# 3_Phase_Controller_V0_2.net
KiCad netlist of a schematic drawn in EAGLE
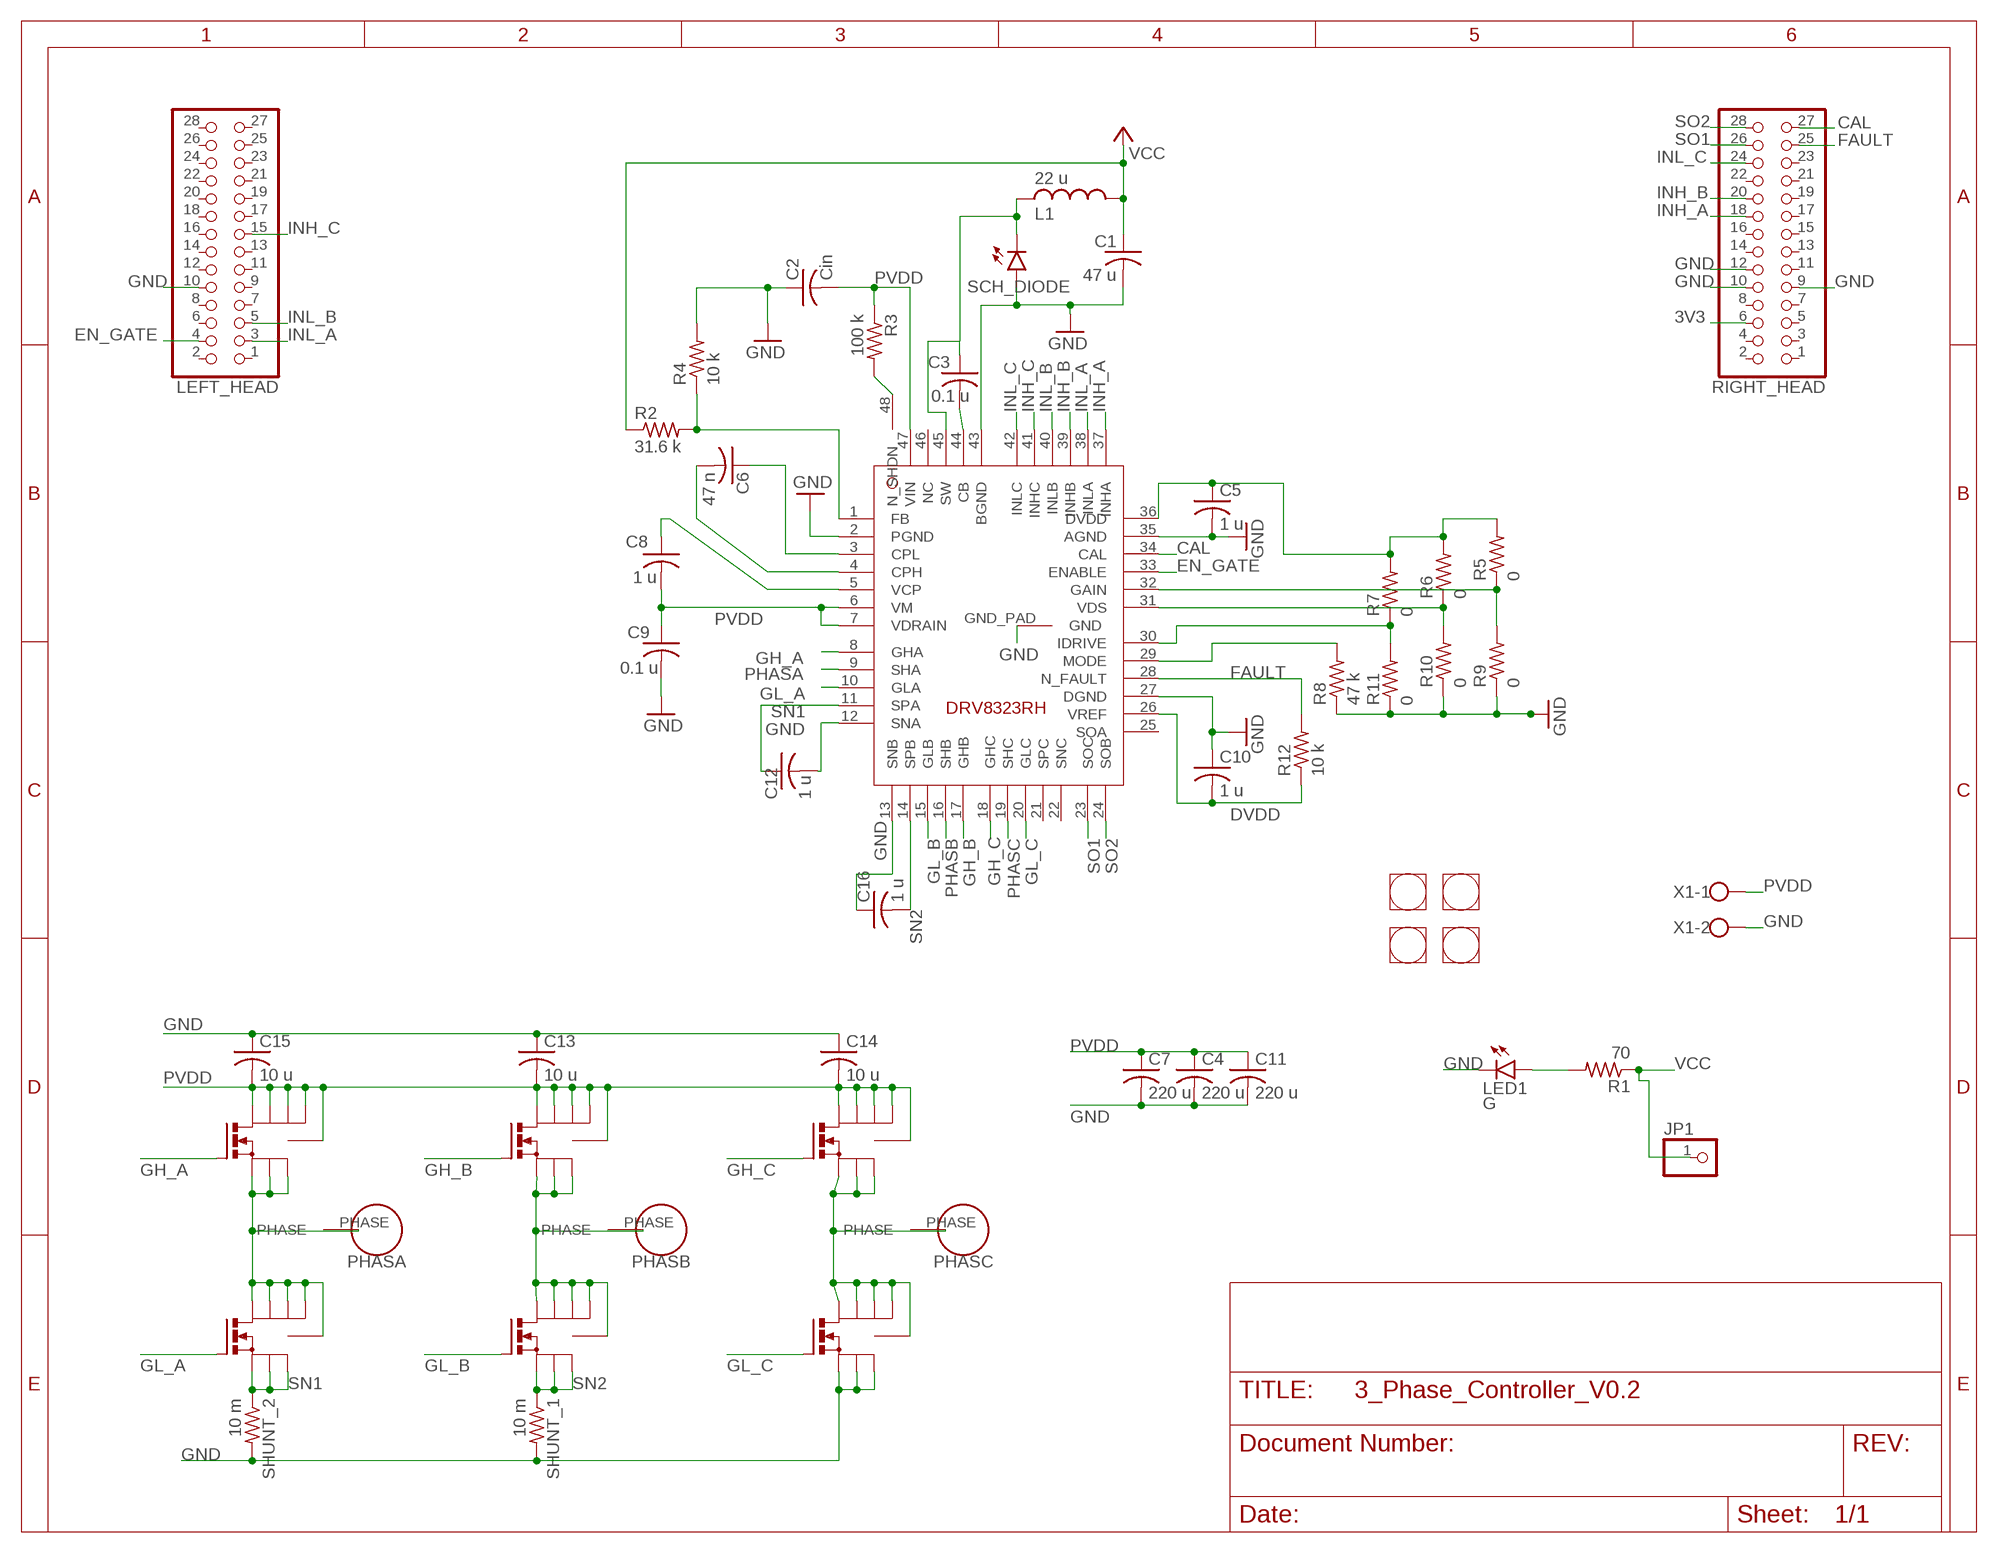
[diagram p0: schematic, sheet 1]

(export (version "E")
  (design (tool "Eeschema 10.0.6"))
  (components
    (comp (ref "A_H")
      (value "SIR178DP")
      (footprint "eagle-import:POWERPAK_SO-8_SINGLE")
      (libsource (lib "eagle-import") (part "SIR178DP"))
    )
    (comp (ref "A_L")
      (value "SIR178DP")
      (footprint "eagle-import:POWERPAK_SO-8_SINGLE")
      (libsource (lib "eagle-import") (part "SIR178DP"))
    )
    (comp (ref "B_H")
      (value "SIR178DP")
      (footprint "eagle-import:POWERPAK_SO-8_SINGLE")
      (libsource (lib "eagle-import") (part "SIR178DP"))
    )
    (comp (ref "B_L")
      (value "SIR178DP")
      (footprint "eagle-import:POWERPAK_SO-8_SINGLE")
      (libsource (lib "eagle-import") (part "SIR178DP"))
    )
    (comp (ref "C1")
      (value "47 u")
      (footprint "eagle-import:C025-024X044")
      (libsource (lib "eagle-import") (part "C-US025-024X044"))
    )
    (comp (ref "C2")
      (value "Cin")
      (footprint "eagle-import:C0805")
      (libsource (lib "eagle-import") (part "C-USC0805"))
    )
    (comp (ref "C3")
      (value "0.1 u")
      (footprint "eagle-import:C0805")
      (libsource (lib "eagle-import") (part "C-USC0805"))
    )
    (comp (ref "C4")
      (value "220 u")
      (footprint "eagle-import:C050-045X075")
      (libsource (lib "eagle-import") (part "C-US050-045X075"))
    )
    (comp (ref "C5")
      (value "1 u")
      (footprint "eagle-import:C0805")
      (libsource (lib "eagle-import") (part "C-USC0805"))
    )
    (comp (ref "C6")
      (value "47 n")
      (footprint "eagle-import:C0805")
      (libsource (lib "eagle-import") (part "C-USC0805"))
    )
    (comp (ref "C7")
      (value "220 u")
      (footprint "eagle-import:C050-045X075")
      (libsource (lib "eagle-import") (part "C-US050-045X075"))
    )
    (comp (ref "C8")
      (value "1 u")
      (footprint "eagle-import:C0805")
      (libsource (lib "eagle-import") (part "C-USC0805"))
    )
    (comp (ref "C9")
      (value "0.1 u")
      (footprint "eagle-import:C0805")
      (libsource (lib "eagle-import") (part "C-USC0805"))
    )
    (comp (ref "C10")
      (value "1 u")
      (footprint "eagle-import:C0805")
      (libsource (lib "eagle-import") (part "C-USC0805"))
    )
    (comp (ref "C11")
      (value "220 u")
      (footprint "eagle-import:C050-045X075")
      (libsource (lib "eagle-import") (part "C-US050-045X075"))
    )
    (comp (ref "C12")
      (value "1 u")
      (footprint "eagle-import:C0805")
      (libsource (lib "eagle-import") (part "C-USC0805"))
    )
    (comp (ref "C13")
      (value "10 u")
      (footprint "eagle-import:C1206")
      (libsource (lib "eagle-import") (part "C-USC1206"))
    )
    (comp (ref "C14")
      (value "10 u")
      (footprint "eagle-import:C1206")
      (libsource (lib "eagle-import") (part "C-USC1206"))
    )
    (comp (ref "C15")
      (value "10 u")
      (footprint "eagle-import:C1206")
      (libsource (lib "eagle-import") (part "C-USC1206"))
    )
    (comp (ref "C16")
      (value "1 u")
      (footprint "eagle-import:C0805")
      (libsource (lib "eagle-import") (part "C-USC0805"))
    )
    (comp (ref "C_H")
      (value "SIR178DP")
      (footprint "eagle-import:POWERPAK_SO-8_SINGLE")
      (libsource (lib "eagle-import") (part "SIR178DP"))
    )
    (comp (ref "C_L")
      (value "SIR178DP")
      (footprint "eagle-import:POWERPAK_SO-8_SINGLE")
      (libsource (lib "eagle-import") (part "SIR178DP"))
    )
    (comp (ref "JP1")
      (value "PINHD-1X1")
      (footprint "eagle-import:1X01")
      (libsource (lib "eagle-import") (part "PINHD-1X1"))
    )
    (comp (ref "L1")
      (value "22 u")
      (footprint "eagle-import:L3225M")
      (libsource (lib "eagle-import") (part "L-USL3225M"))
    )
    (comp (ref "LED1")
      (value "G")
      (footprint "eagle-import:SML0805")
      (libsource (lib "eagle-import") (part "LEDSML0805"))
    )
    (comp (ref "LEFT_HEAD")
      (value "PINHD-2X14")
      (footprint "eagle-import:2X14")
      (libsource (lib "eagle-import") (part "PINHD-2X14"))
    )
    (comp (ref "PHASE_A")
      (value "PHASE_HOLE_V_0.2")
      (footprint "eagle-import:HOLE_V_0.2")
      (libsource (lib "eagle-import") (part "PHASE_HOLE_V_0.2"))
    )
    (comp (ref "PHASE_B")
      (value "PHASE_HOLE_V_0.2")
      (footprint "eagle-import:HOLE_V_0.2")
      (libsource (lib "eagle-import") (part "PHASE_HOLE_V_0.2"))
    )
    (comp (ref "PHASE_C")
      (value "PHASE_HOLE_V_0.2")
      (footprint "eagle-import:HOLE_V_0.2")
      (libsource (lib "eagle-import") (part "PHASE_HOLE_V_0.2"))
    )
    (comp (ref "R1")
      (value "70")
      (footprint "eagle-import:R0805")
      (libsource (lib "eagle-import") (part "R-US_R0805"))
    )
    (comp (ref "R2")
      (value "31.6 k")
      (footprint "eagle-import:R0603")
      (libsource (lib "eagle-import") (part "R-US_R0603"))
    )
    (comp (ref "R3")
      (value "100 k")
      (footprint "eagle-import:R0805")
      (libsource (lib "eagle-import") (part "R-US_R0805"))
    )
    (comp (ref "R4")
      (value "10 k")
      (footprint "eagle-import:R0603")
      (libsource (lib "eagle-import") (part "R-US_R0603"))
    )
    (comp (ref "R5")
      (value "0")
      (footprint "eagle-import:R0603")
      (libsource (lib "eagle-import") (part "R-US_R0603"))
    )
    (comp (ref "R6")
      (value "0")
      (footprint "eagle-import:R0603")
      (libsource (lib "eagle-import") (part "R-US_R0603"))
    )
    (comp (ref "R7")
      (value "0")
      (footprint "eagle-import:R0603")
      (libsource (lib "eagle-import") (part "R-US_R0603"))
    )
    (comp (ref "R8")
      (value "47 k")
      (footprint "eagle-import:R0603")
      (libsource (lib "eagle-import") (part "R-US_R0603"))
    )
    (comp (ref "R9")
      (value "0")
      (footprint "eagle-import:R0603")
      (libsource (lib "eagle-import") (part "R-US_R0603"))
    )
    (comp (ref "R10")
      (value "0")
      (footprint "eagle-import:R0603")
      (libsource (lib "eagle-import") (part "R-US_R0603"))
    )
    (comp (ref "R11")
      (value "0")
      (footprint "eagle-import:R0603")
      (libsource (lib "eagle-import") (part "R-US_R0603"))
    )
    (comp (ref "R12")
      (value "10 k")
      (footprint "eagle-import:R0603")
      (libsource (lib "eagle-import") (part "R-US_R0603"))
    )
    (comp (ref "RIGHT_HEAD")
      (value "PINHD-2X14")
      (footprint "eagle-import:2X14")
      (libsource (lib "eagle-import") (part "PINHD-2X14"))
    )
    (comp (ref "SCH_DIODE")
      (value "LEDCHIP-LED0805")
      (footprint "eagle-import:CHIP-LED0805")
      (libsource (lib "eagle-import") (part "LEDCHIP-LED0805"))
    )
    (comp (ref "SHUNT_1")
      (value "10 m")
      (footprint "eagle-import:R2512")
      (libsource (lib "eagle-import") (part "R-US_R2512"))
    )
    (comp (ref "SHUNT_2")
      (value "10 m")
      (footprint "eagle-import:R2512")
      (libsource (lib "eagle-import") (part "R-US_R2512"))
    )
    (comp (ref "U$1")
      (value "STANDOFF")
      (footprint "eagle-import:STANDOFF")
      (libsource (lib "eagle-import") (part "STANDOFF"))
    )
    (comp (ref "U$2")
      (value "STANDOFF")
      (footprint "eagle-import:STANDOFF")
      (libsource (lib "eagle-import") (part "STANDOFF"))
    )
    (comp (ref "U$3")
      (value "DRV8323RH")
      (footprint "eagle-import:VQFN-RGZ0048A")
      (libsource (lib "eagle-import") (part "DRV8323RH"))
    )
    (comp (ref "U$4")
      (value "STANDOFF")
      (footprint "eagle-import:STANDOFF")
      (libsource (lib "eagle-import") (part "STANDOFF"))
    )
    (comp (ref "U$5")
      (value "STANDOFF")
      (footprint "eagle-import:STANDOFF")
      (libsource (lib "eagle-import") (part "STANDOFF"))
    )
    (comp (ref "X1")
      (value "W237-102")
      (footprint "eagle-import:W237-102")
      (fields (field (name "MPN") "237-102"))
      (libsource (lib "eagle-import") (part "W237-102"))
    )
  )
  (nets
    (net (code "1") (name "/3V3") (class "Default")
      (node (ref "RIGHT_HEAD") (pin "6") (pinfunction "6_6") (pintype "passive"))
    )
    (net (code "2") (name "/CAL") (class "Default")
      (node (ref "RIGHT_HEAD") (pin "27") (pinfunction "27_27") (pintype "passive"))
      (node (ref "U$3") (pin "34") (pinfunction "CAL_34") (pintype "bidirectional"))
    )
    (net (code "3") (name "/DVDD") (class "Default")
      (node (ref "C10") (pin "2") (pinfunction "2_2") (pintype "passive"))
      (node (ref "C5") (pin "1") (pinfunction "1_1") (pintype "passive"))
      (node (ref "R12") (pin "1") (pinfunction "1_1") (pintype "passive"))
      (node (ref "R5") (pin "2") (pinfunction "2_2") (pintype "passive"))
      (node (ref "R6") (pin "2") (pinfunction "2_2") (pintype "passive"))
      (node (ref "R7") (pin "2") (pinfunction "2_2") (pintype "passive"))
      (node (ref "U$3") (pin "26") (pinfunction "VREF_26") (pintype "bidirectional"))
      (node (ref "U$3") (pin "36") (pinfunction "DVDD_36") (pintype "bidirectional"))
    )
    (net (code "4") (name "/EN_GATE") (class "Default")
      (node (ref "LEFT_HEAD") (pin "4") (pinfunction "4_4") (pintype "passive"))
      (node (ref "U$3") (pin "33") (pinfunction "ENABLE_33") (pintype "bidirectional"))
    )
    (net (code "5") (name "/FAULT") (class "Default")
      (node (ref "R12") (pin "2") (pinfunction "2_2") (pintype "passive"))
      (node (ref "RIGHT_HEAD") (pin "25") (pinfunction "25_25") (pintype "passive"))
      (node (ref "U$3") (pin "28") (pinfunction "N_FAULT_28") (pintype "bidirectional"))
    )
    (net (code "6") (name "/GH_A") (class "Default")
      (node (ref "A_H") (pin "GATE") (pinfunction "G_GATE") (pintype "passive"))
      (node (ref "U$3") (pin "8") (pinfunction "GHA_8") (pintype "bidirectional"))
    )
    (net (code "7") (name "/GH_B") (class "Default")
      (node (ref "B_H") (pin "GATE") (pinfunction "G_GATE") (pintype "passive"))
      (node (ref "U$3") (pin "17") (pinfunction "GHB_17") (pintype "bidirectional"))
    )
    (net (code "8") (name "/GH_C") (class "Default")
      (node (ref "C_H") (pin "GATE") (pinfunction "G_GATE") (pintype "passive"))
      (node (ref "U$3") (pin "18") (pinfunction "GHC_18") (pintype "bidirectional"))
    )
    (net (code "9") (name "/GL_A") (class "Default")
      (node (ref "A_L") (pin "GATE") (pinfunction "G_GATE") (pintype "passive"))
      (node (ref "U$3") (pin "10") (pinfunction "GLA_10") (pintype "bidirectional"))
    )
    (net (code "10") (name "/GL_B") (class "Default")
      (node (ref "B_L") (pin "GATE") (pinfunction "G_GATE") (pintype "passive"))
      (node (ref "U$3") (pin "15") (pinfunction "GLB_15") (pintype "bidirectional"))
    )
    (net (code "11") (name "/GL_C") (class "Default")
      (node (ref "C_L") (pin "GATE") (pinfunction "G_GATE") (pintype "passive"))
      (node (ref "U$3") (pin "20") (pinfunction "GLC_20") (pintype "bidirectional"))
    )
    (net (code "12") (name "/INH_A") (class "Default")
      (node (ref "RIGHT_HEAD") (pin "18") (pinfunction "18_18") (pintype "passive"))
      (node (ref "U$3") (pin "37") (pinfunction "INHA_37") (pintype "bidirectional"))
    )
    (net (code "13") (name "/INH_B") (class "Default")
      (node (ref "RIGHT_HEAD") (pin "20") (pinfunction "20_20") (pintype "passive"))
      (node (ref "U$3") (pin "39") (pinfunction "INHB_39") (pintype "bidirectional"))
    )
    (net (code "14") (name "/INH_C") (class "Default")
      (node (ref "LEFT_HEAD") (pin "15") (pinfunction "15_15") (pintype "passive"))
      (node (ref "U$3") (pin "41") (pinfunction "INHC_41") (pintype "bidirectional"))
    )
    (net (code "15") (name "/INL_A") (class "Default")
      (node (ref "LEFT_HEAD") (pin "3") (pinfunction "3_3") (pintype "passive"))
      (node (ref "U$3") (pin "38") (pinfunction "INLA_38") (pintype "bidirectional"))
    )
    (net (code "16") (name "/INL_B") (class "Default")
      (node (ref "LEFT_HEAD") (pin "5") (pinfunction "5_5") (pintype "passive"))
      (node (ref "U$3") (pin "40") (pinfunction "INLB_40") (pintype "bidirectional"))
    )
    (net (code "17") (name "/INL_C") (class "Default")
      (node (ref "RIGHT_HEAD") (pin "24") (pinfunction "24_24") (pintype "passive"))
      (node (ref "U$3") (pin "42") (pinfunction "INLC_42") (pintype "bidirectional"))
    )
    (net (code "18") (name "/PHASA") (class "Default")
      (node (ref "A_H") (pin "S_1") (pinfunction "S_S_1") (pintype "passive"))
      (node (ref "A_H") (pin "S_2") (pinfunction "S1_S_2") (pintype "passive"))
      (node (ref "A_H") (pin "S_3") (pinfunction "S2_S_3") (pintype "passive"))
      (node (ref "A_L") (pin "D_1") (pinfunction "D_D_1") (pintype "passive"))
      (node (ref "A_L") (pin "D_2") (pinfunction "D1_D_2") (pintype "passive"))
      (node (ref "A_L") (pin "D_3") (pinfunction "D2_D_3") (pintype "passive"))
      (node (ref "A_L") (pin "D_4") (pinfunction "D3_D_4") (pintype "passive"))
      (node (ref "A_L") (pin "THRM") (pinfunction "THERMAL_THRM") (pintype "passive"))
      (node (ref "PHASE_A") (pin "PHASE") (pinfunction "PHASE_PHASE") (pintype "bidirectional"))
      (node (ref "U$3") (pin "9") (pinfunction "SHA_9") (pintype "bidirectional"))
    )
    (net (code "19") (name "/PHASB") (class "Default")
      (node (ref "B_H") (pin "S_1") (pinfunction "S_S_1") (pintype "passive"))
      (node (ref "B_H") (pin "S_2") (pinfunction "S1_S_2") (pintype "passive"))
      (node (ref "B_H") (pin "S_3") (pinfunction "S2_S_3") (pintype "passive"))
      (node (ref "B_L") (pin "D_1") (pinfunction "D_D_1") (pintype "passive"))
      (node (ref "B_L") (pin "D_2") (pinfunction "D1_D_2") (pintype "passive"))
      (node (ref "B_L") (pin "D_3") (pinfunction "D2_D_3") (pintype "passive"))
      (node (ref "B_L") (pin "D_4") (pinfunction "D3_D_4") (pintype "passive"))
      (node (ref "B_L") (pin "THRM") (pinfunction "THERMAL_THRM") (pintype "passive"))
      (node (ref "PHASE_B") (pin "PHASE") (pinfunction "PHASE_PHASE") (pintype "bidirectional"))
      (node (ref "U$3") (pin "16") (pinfunction "SHB_16") (pintype "bidirectional"))
    )
    (net (code "20") (name "/PHASC") (class "Default")
      (node (ref "C_H") (pin "S_1") (pinfunction "S_S_1") (pintype "passive"))
      (node (ref "C_H") (pin "S_2") (pinfunction "S1_S_2") (pintype "passive"))
      (node (ref "C_H") (pin "S_3") (pinfunction "S2_S_3") (pintype "passive"))
      (node (ref "C_L") (pin "D_1") (pinfunction "D_D_1") (pintype "passive"))
      (node (ref "C_L") (pin "D_2") (pinfunction "D1_D_2") (pintype "passive"))
      (node (ref "C_L") (pin "D_3") (pinfunction "D2_D_3") (pintype "passive"))
      (node (ref "C_L") (pin "D_4") (pinfunction "D3_D_4") (pintype "passive"))
      (node (ref "C_L") (pin "THRM") (pinfunction "THERMAL_THRM") (pintype "passive"))
      (node (ref "PHASE_C") (pin "PHASE") (pinfunction "PHASE_PHASE") (pintype "bidirectional"))
      (node (ref "U$3") (pin "19") (pinfunction "SHC_19") (pintype "bidirectional"))
    )
    (net (code "21") (name "/PVDD") (class "Default")
      (node (ref "A_H") (pin "D_1") (pinfunction "D_D_1") (pintype "passive"))
      (node (ref "A_H") (pin "D_2") (pinfunction "D1_D_2") (pintype "passive"))
      (node (ref "A_H") (pin "D_3") (pinfunction "D2_D_3") (pintype "passive"))
      (node (ref "A_H") (pin "D_4") (pinfunction "D3_D_4") (pintype "passive"))
      (node (ref "A_H") (pin "THRM") (pinfunction "THERMAL_THRM") (pintype "passive"))
      (node (ref "B_H") (pin "D_1") (pinfunction "D_D_1") (pintype "passive"))
      (node (ref "B_H") (pin "D_2") (pinfunction "D1_D_2") (pintype "passive"))
      (node (ref "B_H") (pin "D_3") (pinfunction "D2_D_3") (pintype "passive"))
      (node (ref "B_H") (pin "D_4") (pinfunction "D3_D_4") (pintype "passive"))
      (node (ref "B_H") (pin "THRM") (pinfunction "THERMAL_THRM") (pintype "passive"))
      (node (ref "C11") (pin "1") (pinfunction "1_1") (pintype "passive"))
      (node (ref "C13") (pin "2") (pinfunction "2_2") (pintype "passive"))
      (node (ref "C14") (pin "2") (pinfunction "2_2") (pintype "passive"))
      (node (ref "C15") (pin "2") (pinfunction "2_2") (pintype "passive"))
      (node (ref "C2") (pin "2") (pinfunction "2_2") (pintype "passive"))
      (node (ref "C4") (pin "1") (pinfunction "1_1") (pintype "passive"))
      (node (ref "C7") (pin "1") (pinfunction "1_1") (pintype "passive"))
      (node (ref "C8") (pin "2") (pinfunction "2_2") (pintype "passive"))
      (node (ref "C9") (pin "1") (pinfunction "1_1") (pintype "passive"))
      (node (ref "C_H") (pin "D_1") (pinfunction "D_D_1") (pintype "passive"))
      (node (ref "C_H") (pin "D_2") (pinfunction "D1_D_2") (pintype "passive"))
      (node (ref "C_H") (pin "D_3") (pinfunction "D2_D_3") (pintype "passive"))
      (node (ref "C_H") (pin "D_4") (pinfunction "D3_D_4") (pintype "passive"))
      (node (ref "C_H") (pin "THRM") (pinfunction "THERMAL_THRM") (pintype "passive"))
      (node (ref "R3") (pin "1") (pinfunction "1_1") (pintype "passive"))
      (node (ref "U$3") (pin "47") (pinfunction "VIN_47") (pintype "bidirectional"))
      (node (ref "U$3") (pin "6") (pinfunction "VM_6") (pintype "bidirectional"))
      (node (ref "U$3") (pin "7") (pinfunction "VDRAIN_7") (pintype "bidirectional"))
      (node (ref "X1") (pin "1") (pinfunction "KL_1") (pintype "passive"))
    )
    (net (code "22") (name "/SN1") (class "Default")
      (node (ref "A_L") (pin "S_1") (pinfunction "S_S_1") (pintype "passive"))
      (node (ref "A_L") (pin "S_2") (pinfunction "S1_S_2") (pintype "passive"))
      (node (ref "A_L") (pin "S_3") (pinfunction "S2_S_3") (pintype "passive"))
      (node (ref "C12") (pin "1") (pinfunction "1_1") (pintype "passive"))
      (node (ref "SHUNT_2") (pin "1") (pinfunction "1_1") (pintype "passive"))
      (node (ref "U$3") (pin "11") (pinfunction "SPA_11") (pintype "bidirectional"))
    )
    (net (code "23") (name "/SN2") (class "Default")
      (node (ref "B_L") (pin "S_1") (pinfunction "S_S_1") (pintype "passive"))
      (node (ref "B_L") (pin "S_2") (pinfunction "S1_S_2") (pintype "passive"))
      (node (ref "B_L") (pin "S_3") (pinfunction "S2_S_3") (pintype "passive"))
      (node (ref "C16") (pin "2") (pinfunction "2_2") (pintype "passive"))
      (node (ref "SHUNT_1") (pin "1") (pinfunction "1_1") (pintype "passive"))
      (node (ref "U$3") (pin "14") (pinfunction "SPB_14") (pintype "bidirectional"))
    )
    (net (code "24") (name "/SO1") (class "Default")
      (node (ref "RIGHT_HEAD") (pin "26") (pinfunction "26_26") (pintype "passive"))
      (node (ref "U$3") (pin "23") (pinfunction "SOC_23") (pintype "bidirectional"))
    )
    (net (code "25") (name "/SO2") (class "Default")
      (node (ref "RIGHT_HEAD") (pin "28") (pinfunction "28_28") (pintype "passive"))
      (node (ref "U$3") (pin "24") (pinfunction "SOB_24") (pintype "bidirectional"))
    )
    (net (code "26") (name "GND") (class "Default")
      (node (ref "C1") (pin "2") (pinfunction "2_2") (pintype "passive"))
      (node (ref "C10") (pin "1") (pinfunction "1_1") (pintype "passive"))
      (node (ref "C11") (pin "2") (pinfunction "2_2") (pintype "passive"))
      (node (ref "C12") (pin "2") (pinfunction "2_2") (pintype "passive"))
      (node (ref "C13") (pin "1") (pinfunction "1_1") (pintype "passive"))
      (node (ref "C14") (pin "1") (pinfunction "1_1") (pintype "passive"))
      (node (ref "C15") (pin "1") (pinfunction "1_1") (pintype "passive"))
      (node (ref "C16") (pin "1") (pinfunction "1_1") (pintype "passive"))
      (node (ref "C2") (pin "1") (pinfunction "1_1") (pintype "passive"))
      (node (ref "C4") (pin "2") (pinfunction "2_2") (pintype "passive"))
      (node (ref "C5") (pin "2") (pinfunction "2_2") (pintype "passive"))
      (node (ref "C7") (pin "2") (pinfunction "2_2") (pintype "passive"))
      (node (ref "C9") (pin "2") (pinfunction "2_2") (pintype "passive"))
      (node (ref "C_L") (pin "S_1") (pinfunction "S_S_1") (pintype "passive"))
      (node (ref "C_L") (pin "S_2") (pinfunction "S1_S_2") (pintype "passive"))
      (node (ref "C_L") (pin "S_3") (pinfunction "S2_S_3") (pintype "passive"))
      (node (ref "LED1") (pin "C") (pinfunction "C_C") (pintype "passive"))
      (node (ref "LEFT_HEAD") (pin "10") (pinfunction "10_10") (pintype "passive"))
      (node (ref "R10") (pin "1") (pinfunction "1_1") (pintype "passive"))
      (node (ref "R11") (pin "1") (pinfunction "1_1") (pintype "passive"))
      (node (ref "R4") (pin "2") (pinfunction "2_2") (pintype "passive"))
      (node (ref "R8") (pin "1") (pinfunction "1_1") (pintype "passive"))
      (node (ref "R9") (pin "1") (pinfunction "1_1") (pintype "passive"))
      (node (ref "RIGHT_HEAD") (pin "10") (pinfunction "10_10") (pintype "passive"))
      (node (ref "RIGHT_HEAD") (pin "12") (pinfunction "12_12") (pintype "passive"))
      (node (ref "RIGHT_HEAD") (pin "9") (pinfunction "9_9") (pintype "passive"))
      (node (ref "SCH_DIODE") (pin "A") (pinfunction "A_A") (pintype "passive"))
      (node (ref "SHUNT_1") (pin "2") (pinfunction "2_2") (pintype "passive"))
      (node (ref "SHUNT_2") (pin "2") (pinfunction "2_2") (pintype "passive"))
      (node (ref "U$3") (pin "12") (pinfunction "SNA_12") (pintype "bidirectional"))
      (node (ref "U$3") (pin "13") (pinfunction "SNB_13") (pintype "bidirectional"))
      (node (ref "U$3") (pin "2") (pinfunction "PGND_2") (pintype "bidirectional"))
      (node (ref "U$3") (pin "27") (pinfunction "DGND_27") (pintype "bidirectional"))
      (node (ref "U$3") (pin "35") (pinfunction "AGND_35") (pintype "bidirectional"))
      (node (ref "U$3") (pin "43") (pinfunction "BGND_43") (pintype "bidirectional"))
      (node (ref "U$3") (pin "GND_PAD") (pinfunction "GND_GND_PAD") (pintype "bidirectional"))
      (node (ref "X1") (pin "2") (pinfunction "KL_2") (pintype "passive"))
    )
    (net (code "27") (name "Net-(LED1-PadA)") (class "Default")
      (node (ref "LED1") (pin "A") (pinfunction "A_A") (pintype "passive"))
      (node (ref "R1") (pin "2") (pinfunction "2_2") (pintype "passive"))
    )
    (net (code "28") (name "Net-(U$3-CB)") (class "Default")
      (node (ref "C3") (pin "2") (pinfunction "2_2") (pintype "passive"))
      (node (ref "U$3") (pin "44") (pinfunction "CB_44") (pintype "bidirectional"))
    )
    (net (code "29") (name "Net-(U$3-CPH)") (class "Default")
      (node (ref "C6") (pin "2") (pinfunction "2_2") (pintype "passive"))
      (node (ref "U$3") (pin "4") (pinfunction "CPH_4") (pintype "bidirectional"))
    )
    (net (code "30") (name "Net-(U$3-CPL)") (class "Default")
      (node (ref "C6") (pin "1") (pinfunction "1_1") (pintype "passive"))
      (node (ref "U$3") (pin "3") (pinfunction "CPL_3") (pintype "bidirectional"))
    )
    (net (code "31") (name "Net-(U$3-FB)") (class "Default")
      (node (ref "R2") (pin "2") (pinfunction "2_2") (pintype "passive"))
      (node (ref "R4") (pin "1") (pinfunction "1_1") (pintype "passive"))
      (node (ref "U$3") (pin "1") (pinfunction "FB_1") (pintype "bidirectional"))
    )
    (net (code "32") (name "Net-(U$3-GAIN)") (class "Default")
      (node (ref "R5") (pin "1") (pinfunction "1_1") (pintype "passive"))
      (node (ref "R9") (pin "2") (pinfunction "2_2") (pintype "passive"))
      (node (ref "U$3") (pin "32") (pinfunction "GAIN_32") (pintype "bidirectional"))
    )
    (net (code "33") (name "Net-(U$3-IDRIVE)") (class "Default")
      (node (ref "R11") (pin "2") (pinfunction "2_2") (pintype "passive"))
      (node (ref "R7") (pin "1") (pinfunction "1_1") (pintype "passive"))
      (node (ref "U$3") (pin "30") (pinfunction "IDRIVE_30") (pintype "bidirectional"))
    )
    (net (code "34") (name "Net-(U$3-MODE)") (class "Default")
      (node (ref "R8") (pin "2") (pinfunction "2_2") (pintype "passive"))
      (node (ref "U$3") (pin "29") (pinfunction "MODE_29") (pintype "bidirectional"))
    )
    (net (code "35") (name "Net-(U$3-N_SHDN)") (class "Default")
      (node (ref "R3") (pin "2") (pinfunction "2_2") (pintype "passive"))
      (node (ref "U$3") (pin "48") (pinfunction "N_SHDN_48") (pintype "bidirectional"))
    )
    (net (code "36") (name "Net-(U$3-SW)") (class "Default")
      (node (ref "C3") (pin "1") (pinfunction "1_1") (pintype "passive"))
      (node (ref "L1") (pin "2") (pinfunction "2_2") (pintype "passive"))
      (node (ref "SCH_DIODE") (pin "C") (pinfunction "C_C") (pintype "passive"))
      (node (ref "U$3") (pin "45") (pinfunction "SW_45") (pintype "bidirectional"))
    )
    (net (code "37") (name "Net-(U$3-VCP)") (class "Default")
      (node (ref "C8") (pin "1") (pinfunction "1_1") (pintype "passive"))
      (node (ref "U$3") (pin "5") (pinfunction "VCP_5") (pintype "bidirectional"))
    )
    (net (code "38") (name "Net-(U$3-VDS)") (class "Default")
      (node (ref "R10") (pin "2") (pinfunction "2_2") (pintype "passive"))
      (node (ref "R6") (pin "1") (pinfunction "1_1") (pintype "passive"))
      (node (ref "U$3") (pin "31") (pinfunction "VDS_31") (pintype "bidirectional"))
    )
    (net (code "39") (name "VCC") (class "Default")
      (node (ref "C1") (pin "1") (pinfunction "1_1") (pintype "passive"))
      (node (ref "JP1") (pin "1") (pinfunction "1_1") (pintype "passive"))
      (node (ref "L1") (pin "1") (pinfunction "1_1") (pintype "passive"))
      (node (ref "R1") (pin "1") (pinfunction "1_1") (pintype "passive"))
      (node (ref "R2") (pin "1") (pinfunction "1_1") (pintype "passive"))
    )
    (net (code "40") (name "unconnected-(LEFT_HEAD-Pad1)") (class "Default")
      (node (ref "LEFT_HEAD") (pin "1") (pinfunction "1_1") (pintype "passive"))
    )
    (net (code "41") (name "unconnected-(LEFT_HEAD-Pad2)") (class "Default")
      (node (ref "LEFT_HEAD") (pin "2") (pinfunction "2_2") (pintype "passive"))
    )
    (net (code "42") (name "unconnected-(LEFT_HEAD-Pad6)") (class "Default")
      (node (ref "LEFT_HEAD") (pin "6") (pinfunction "6_6") (pintype "passive"))
    )
    (net (code "43") (name "unconnected-(LEFT_HEAD-Pad7)") (class "Default")
      (node (ref "LEFT_HEAD") (pin "7") (pinfunction "7_7") (pintype "passive"))
    )
    (net (code "44") (name "unconnected-(LEFT_HEAD-Pad8)") (class "Default")
      (node (ref "LEFT_HEAD") (pin "8") (pinfunction "8_8") (pintype "passive"))
    )
    (net (code "45") (name "unconnected-(LEFT_HEAD-Pad9)") (class "Default")
      (node (ref "LEFT_HEAD") (pin "9") (pinfunction "9_9") (pintype "passive"))
    )
    (net (code "46") (name "unconnected-(LEFT_HEAD-Pad11)") (class "Default")
      (node (ref "LEFT_HEAD") (pin "11") (pinfunction "11_11") (pintype "passive"))
    )
    (net (code "47") (name "unconnected-(LEFT_HEAD-Pad12)") (class "Default")
      (node (ref "LEFT_HEAD") (pin "12") (pinfunction "12_12") (pintype "passive"))
    )
    (net (code "48") (name "unconnected-(LEFT_HEAD-Pad13)") (class "Default")
      (node (ref "LEFT_HEAD") (pin "13") (pinfunction "13_13") (pintype "passive"))
    )
    (net (code "49") (name "unconnected-(LEFT_HEAD-Pad14)") (class "Default")
      (node (ref "LEFT_HEAD") (pin "14") (pinfunction "14_14") (pintype "passive"))
    )
    (net (code "50") (name "unconnected-(LEFT_HEAD-Pad16)") (class "Default")
      (node (ref "LEFT_HEAD") (pin "16") (pinfunction "16_16") (pintype "passive"))
    )
    (net (code "51") (name "unconnected-(LEFT_HEAD-Pad17)") (class "Default")
      (node (ref "LEFT_HEAD") (pin "17") (pinfunction "17_17") (pintype "passive"))
    )
    (net (code "52") (name "unconnected-(LEFT_HEAD-Pad18)") (class "Default")
      (node (ref "LEFT_HEAD") (pin "18") (pinfunction "18_18") (pintype "passive"))
    )
    (net (code "53") (name "unconnected-(LEFT_HEAD-Pad19)") (class "Default")
      (node (ref "LEFT_HEAD") (pin "19") (pinfunction "19_19") (pintype "passive"))
    )
    (net (code "54") (name "unconnected-(LEFT_HEAD-Pad20)") (class "Default")
      (node (ref "LEFT_HEAD") (pin "20") (pinfunction "20_20") (pintype "passive"))
    )
    (net (code "55") (name "unconnected-(LEFT_HEAD-Pad21)") (class "Default")
      (node (ref "LEFT_HEAD") (pin "21") (pinfunction "21_21") (pintype "passive"))
    )
    (net (code "56") (name "unconnected-(LEFT_HEAD-Pad22)") (class "Default")
      (node (ref "LEFT_HEAD") (pin "22") (pinfunction "22_22") (pintype "passive"))
    )
    (net (code "57") (name "unconnected-(LEFT_HEAD-Pad23)") (class "Default")
      (node (ref "LEFT_HEAD") (pin "23") (pinfunction "23_23") (pintype "passive"))
    )
    (net (code "58") (name "unconnected-(LEFT_HEAD-Pad24)") (class "Default")
      (node (ref "LEFT_HEAD") (pin "24") (pinfunction "24_24") (pintype "passive"))
    )
    (net (code "59") (name "unconnected-(LEFT_HEAD-Pad25)") (class "Default")
      (node (ref "LEFT_HEAD") (pin "25") (pinfunction "25_25") (pintype "passive"))
    )
    (net (code "60") (name "unconnected-(LEFT_HEAD-Pad26)") (class "Default")
      (node (ref "LEFT_HEAD") (pin "26") (pinfunction "26_26") (pintype "passive"))
    )
    (net (code "61") (name "unconnected-(LEFT_HEAD-Pad27)") (class "Default")
      (node (ref "LEFT_HEAD") (pin "27") (pinfunction "27_27") (pintype "passive"))
    )
    (net (code "62") (name "unconnected-(LEFT_HEAD-Pad28)") (class "Default")
      (node (ref "LEFT_HEAD") (pin "28") (pinfunction "28_28") (pintype "passive"))
    )
    (net (code "63") (name "unconnected-(RIGHT_HEAD-Pad1)") (class "Default")
      (node (ref "RIGHT_HEAD") (pin "1") (pinfunction "1_1") (pintype "passive"))
    )
    (net (code "64") (name "unconnected-(RIGHT_HEAD-Pad2)") (class "Default")
      (node (ref "RIGHT_HEAD") (pin "2") (pinfunction "2_2") (pintype "passive"))
    )
    (net (code "65") (name "unconnected-(RIGHT_HEAD-Pad3)") (class "Default")
      (node (ref "RIGHT_HEAD") (pin "3") (pinfunction "3_3") (pintype "passive"))
    )
    (net (code "66") (name "unconnected-(RIGHT_HEAD-Pad4)") (class "Default")
      (node (ref "RIGHT_HEAD") (pin "4") (pinfunction "4_4") (pintype "passive"))
    )
    (net (code "67") (name "unconnected-(RIGHT_HEAD-Pad5)") (class "Default")
      (node (ref "RIGHT_HEAD") (pin "5") (pinfunction "5_5") (pintype "passive"))
    )
    (net (code "68") (name "unconnected-(RIGHT_HEAD-Pad7)") (class "Default")
      (node (ref "RIGHT_HEAD") (pin "7") (pinfunction "7_7") (pintype "passive"))
    )
    (net (code "69") (name "unconnected-(RIGHT_HEAD-Pad8)") (class "Default")
      (node (ref "RIGHT_HEAD") (pin "8") (pinfunction "8_8") (pintype "passive"))
    )
    (net (code "70") (name "unconnected-(RIGHT_HEAD-Pad11)") (class "Default")
      (node (ref "RIGHT_HEAD") (pin "11") (pinfunction "11_11") (pintype "passive"))
    )
    (net (code "71") (name "unconnected-(RIGHT_HEAD-Pad13)") (class "Default")
      (node (ref "RIGHT_HEAD") (pin "13") (pinfunction "13_13") (pintype "passive"))
    )
    (net (code "72") (name "unconnected-(RIGHT_HEAD-Pad14)") (class "Default")
      (node (ref "RIGHT_HEAD") (pin "14") (pinfunction "14_14") (pintype "passive"))
    )
    (net (code "73") (name "unconnected-(RIGHT_HEAD-Pad15)") (class "Default")
      (node (ref "RIGHT_HEAD") (pin "15") (pinfunction "15_15") (pintype "passive"))
    )
    (net (code "74") (name "unconnected-(RIGHT_HEAD-Pad16)") (class "Default")
      (node (ref "RIGHT_HEAD") (pin "16") (pinfunction "16_16") (pintype "passive"))
    )
    (net (code "75") (name "unconnected-(RIGHT_HEAD-Pad17)") (class "Default")
      (node (ref "RIGHT_HEAD") (pin "17") (pinfunction "17_17") (pintype "passive"))
    )
    (net (code "76") (name "unconnected-(RIGHT_HEAD-Pad19)") (class "Default")
      (node (ref "RIGHT_HEAD") (pin "19") (pinfunction "19_19") (pintype "passive"))
    )
    (net (code "77") (name "unconnected-(RIGHT_HEAD-Pad21)") (class "Default")
      (node (ref "RIGHT_HEAD") (pin "21") (pinfunction "21_21") (pintype "passive"))
    )
    (net (code "78") (name "unconnected-(RIGHT_HEAD-Pad22)") (class "Default")
      (node (ref "RIGHT_HEAD") (pin "22") (pinfunction "22_22") (pintype "passive"))
    )
    (net (code "79") (name "unconnected-(RIGHT_HEAD-Pad23)") (class "Default")
      (node (ref "RIGHT_HEAD") (pin "23") (pinfunction "23_23") (pintype "passive"))
    )
    (net (code "80") (name "unconnected-(U$3-NC-Pad46)") (class "Default")
      (node (ref "U$3") (pin "46") (pinfunction "NC_46") (pintype "bidirectional"))
    )
    (net (code "81") (name "unconnected-(U$3-SNC-Pad22)") (class "Default")
      (node (ref "U$3") (pin "22") (pinfunction "SNC_22") (pintype "bidirectional"))
    )
    (net (code "82") (name "unconnected-(U$3-SOA-Pad25)") (class "Default")
      (node (ref "U$3") (pin "25") (pinfunction "SOA_25") (pintype "bidirectional"))
    )
    (net (code "83") (name "unconnected-(U$3-SPC-Pad21)") (class "Default")
      (node (ref "U$3") (pin "21") (pinfunction "SPC_21") (pintype "bidirectional"))
    )
  )
)
